# Pizza_IO.net
KiCad netlist of a schematic drawn in Altium Designer
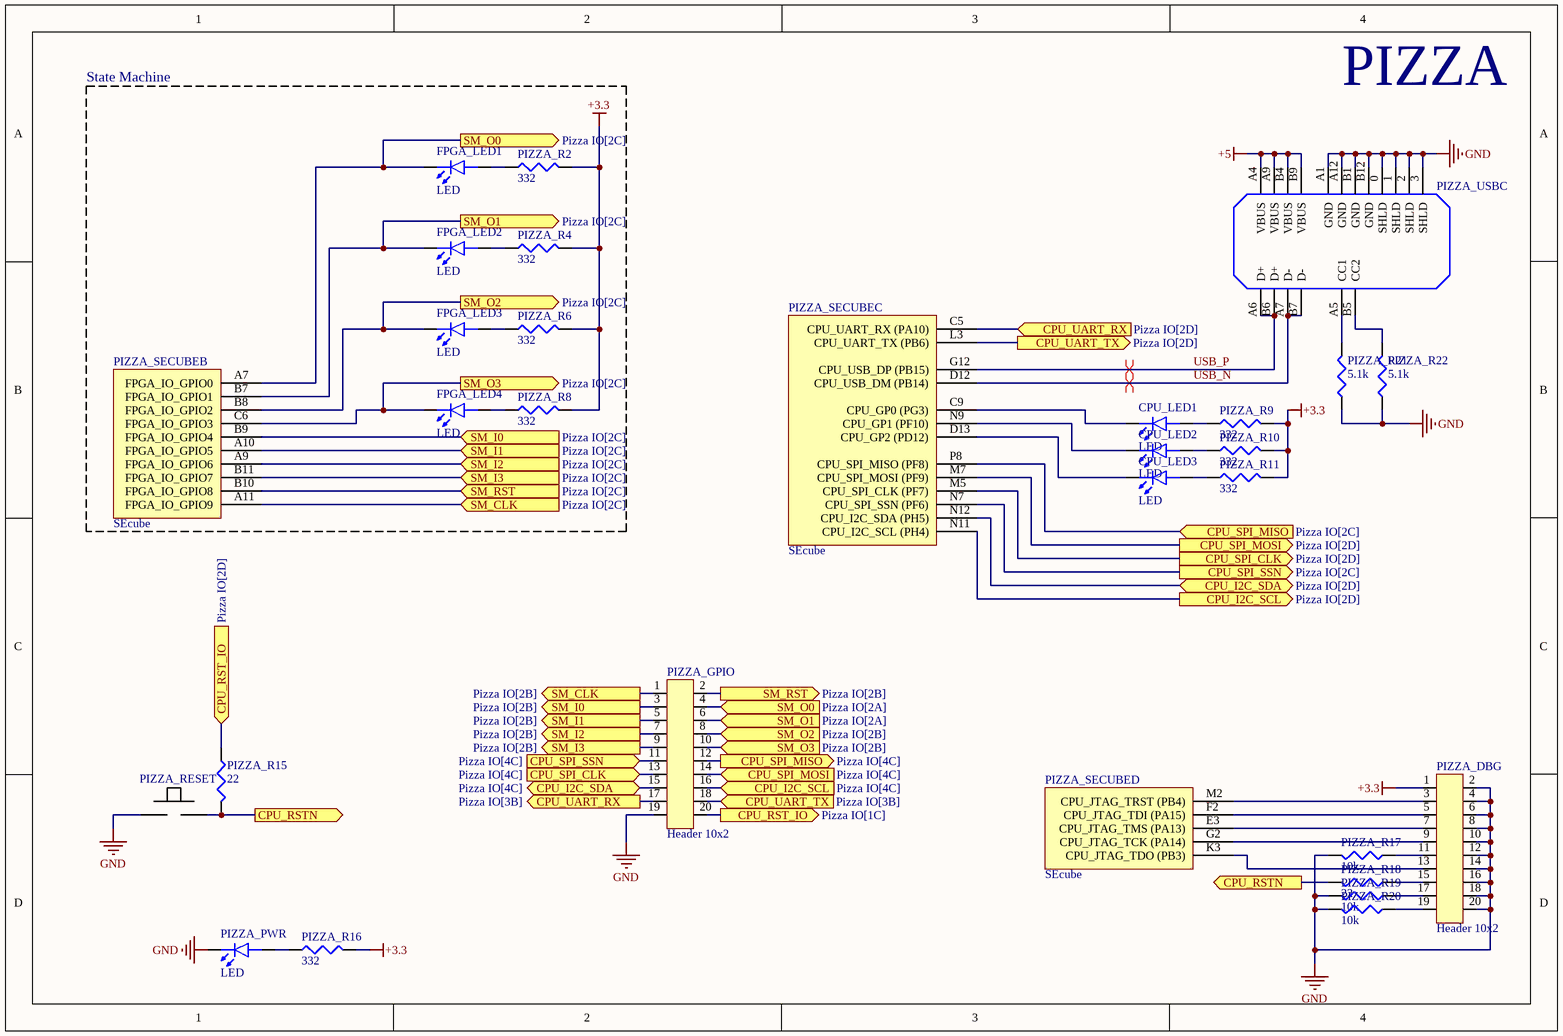
[diagram p0: Pizza IO.SchDoc]

(export (version "E")
  (design (tool "Eeschema 10.0.6"))
  (components
    (comp (ref "CPU_LED1") (value "LED") (footprint "LED0603P") (libsource (lib "ECSC2024") (part "LED")))
    (comp (ref "CPU_LED2") (value "LED") (footprint "LED0603P") (libsource (lib "ECSC2024") (part "LED")))
    (comp (ref "CPU_LED3") (value "LED") (footprint "LED0603P") (libsource (lib "ECSC2024") (part "LED")))
    (comp (ref "FPGA_LED1") (value "LED") (footprint "LED0603P") (libsource (lib "ECSC2024") (part "LED")))
    (comp (ref "FPGA_LED2") (value "LED") (footprint "LED0603P") (libsource (lib "ECSC2024") (part "LED")))
    (comp (ref "FPGA_LED3") (value "LED") (footprint "LED0603P") (libsource (lib "ECSC2024") (part "LED")))
    (comp (ref "FPGA_LED4") (value "LED") (footprint "LED0603P") (libsource (lib "ECSC2024") (part "LED")))
    (comp (ref "PIZZA_DBG")
      (value "Header 10x2")
      (footprint "HEADER10x2")
      (libsource (lib "ECSC2024") (part "Header 10x2"))
    )
    (comp (ref "PIZZA_GPIO")
      (value "Header 10x2")
      (footprint "HEADER10x2")
      (libsource (lib "ECSC2024") (part "Header 10x2"))
    )
    (comp (ref "PIZZA_PWR") (value "LED") (footprint "LED0603P") (libsource (lib "ECSC2024") (part "LED")))
    (comp (ref "PIZZA_R2") (value "332") (footprint "R0402") (libsource (lib "ECSC2024") (part "R")))
    (comp (ref "PIZZA_R4") (value "332") (footprint "R0402") (libsource (lib "ECSC2024") (part "R")))
    (comp (ref "PIZZA_R6") (value "332") (footprint "R0402") (libsource (lib "ECSC2024") (part "R")))
    (comp (ref "PIZZA_R8") (value "332") (footprint "R0402") (libsource (lib "ECSC2024") (part "R")))
    (comp (ref "PIZZA_R9") (value "332") (footprint "R0402") (libsource (lib "ECSC2024") (part "R")))
    (comp (ref "PIZZA_R10") (value "332") (footprint "R0402") (libsource (lib "ECSC2024") (part "R")))
    (comp (ref "PIZZA_R11") (value "332") (footprint "R0402") (libsource (lib "ECSC2024") (part "R")))
    (comp (ref "PIZZA_R15") (value "22") (footprint "R0402") (libsource (lib "ECSC2024") (part "R")))
    (comp (ref "PIZZA_R16") (value "332") (footprint "R0402") (libsource (lib "ECSC2024") (part "R")))
    (comp (ref "PIZZA_R17") (value "10k") (footprint "R0402") (libsource (lib "ECSC2024") (part "R")))
    (comp (ref "PIZZA_R18") (value "22") (footprint "R0402") (libsource (lib "ECSC2024") (part "R")))
    (comp (ref "PIZZA_R19") (value "10k") (footprint "R0402") (libsource (lib "ECSC2024") (part "R")))
    (comp (ref "PIZZA_R20") (value "10k") (footprint "R0402") (libsource (lib "ECSC2024") (part "R")))
    (comp (ref "PIZZA_R21") (value "5.1k") (footprint "R0402") (libsource (lib "ECSC2024") (part "R")))
    (comp (ref "PIZZA_R22") (value "5.1k") (footprint "R0402") (libsource (lib "ECSC2024") (part "R")))
    (comp (ref "PIZZA_RESET")
      (value "BTN")
      (footprint "TS1088AR02016")
      (libsource (lib "ECSC2024") (part "BTN"))
    )
    (comp (ref "PIZZA_SECUBE")
      (value "SEcube")
      (footprint "SEcube")
      (libsource (lib "ECSC2024") (part "SEcube"))
    )
    (comp (ref "PIZZA_USBC")
      (value "USBC")
      (footprint "USB-TYPE-C-018")
      (libsource (lib "ECSC2024") (part "USBC"))
    )
  )
  (nets
    (net (code "1") (name "+3.3") (class "Default")
      (node (ref "PIZZA_DBG") (pin "1") (pintype "passive"))
      (node (ref "PIZZA_R10") (pin "2") (pinfunction "2_2") (pintype "passive"))
      (node (ref "PIZZA_R11") (pin "2") (pinfunction "2_2") (pintype "passive"))
      (node (ref "PIZZA_R16") (pin "2") (pinfunction "2_2") (pintype "passive"))
      (node (ref "PIZZA_R2") (pin "2") (pinfunction "2_2") (pintype "passive"))
      (node (ref "PIZZA_R4") (pin "2") (pinfunction "2_2") (pintype "passive"))
      (node (ref "PIZZA_R6") (pin "2") (pinfunction "2_2") (pintype "passive"))
      (node (ref "PIZZA_R8") (pin "2") (pinfunction "2_2") (pintype "passive"))
      (node (ref "PIZZA_R9") (pin "2") (pinfunction "2_2") (pintype "passive"))
    )
    (net (code "2") (name "+5") (class "Default")
      (node (ref "PIZZA_USBC") (pin "A4") (pinfunction "VBUS_A4") (pintype "passive"))
      (node (ref "PIZZA_USBC") (pin "A9") (pinfunction "VBUS_A9") (pintype "passive"))
      (node (ref "PIZZA_USBC") (pin "B4") (pinfunction "VBUS_B4") (pintype "passive"))
      (node (ref "PIZZA_USBC") (pin "B9") (pinfunction "VBUS_B9") (pintype "passive"))
    )
    (net (code "3") (name "/CPU_I2C_SCL") (class "Default")
      (node (ref "PIZZA_GPIO") (pin "16") (pintype "passive"))
      (node (ref "PIZZA_SECUBE") (pin "N11") (pinfunction "CPU_I2C_SCL_(PH4)_N11") (pintype "passive"))
    )
    (net (code "4") (name "/CPU_I2C_SDA") (class "Default")
      (node (ref "PIZZA_GPIO") (pin "15") (pintype "passive"))
      (node (ref "PIZZA_SECUBE") (pin "N12") (pinfunction "CPU_I2C_SDA_(PH5)_N12") (pintype "passive"))
    )
    (net (code "5") (name "/CPU_RSTN") (class "Default")
      (node (ref "PIZZA_R15") (pin "2") (pinfunction "2_2") (pintype "passive"))
      (node (ref "PIZZA_R18") (pin "2") (pinfunction "2_2") (pintype "passive"))
      (node (ref "PIZZA_RESET") (pin "2") (pinfunction "2_2") (pintype "passive"))
    )
    (net (code "6") (name "/CPU_RST_IO") (class "Default")
      (node (ref "PIZZA_GPIO") (pin "20") (pintype "passive"))
      (node (ref "PIZZA_R15") (pin "1") (pinfunction "1_1") (pintype "passive"))
    )
    (net (code "7") (name "/CPU_SPI_CLK") (class "Default")
      (node (ref "PIZZA_GPIO") (pin "13") (pintype "passive"))
      (node (ref "PIZZA_SECUBE") (pin "M5") (pinfunction "CPU_SPI_CLK_(PF7)_M5") (pintype "passive"))
    )
    (net (code "8") (name "/CPU_SPI_MISO") (class "Default")
      (node (ref "PIZZA_GPIO") (pin "12") (pintype "passive"))
      (node (ref "PIZZA_SECUBE") (pin "P8") (pinfunction "CPU_SPI_MISO_(PF8)_P8") (pintype "passive"))
    )
    (net (code "9") (name "/CPU_SPI_MOSI") (class "Default")
      (node (ref "PIZZA_GPIO") (pin "14") (pintype "passive"))
      (node (ref "PIZZA_SECUBE") (pin "M7") (pinfunction "CPU_SPI_MOSI_(PF9)_M7") (pintype "passive"))
    )
    (net (code "10") (name "/CPU_SPI_SSN") (class "Default")
      (node (ref "PIZZA_GPIO") (pin "11") (pintype "passive"))
      (node (ref "PIZZA_SECUBE") (pin "N7") (pinfunction "CPU_SPI_SSN_(PF6)_N7") (pintype "passive"))
    )
    (net (code "11") (name "/CPU_UART_RX") (class "Default")
      (node (ref "PIZZA_GPIO") (pin "17") (pintype "passive"))
      (node (ref "PIZZA_SECUBE") (pin "C5") (pinfunction "CPU_UART_RX_(PA10)_C5") (pintype "passive"))
    )
    (net (code "12") (name "/CPU_UART_TX") (class "Default")
      (node (ref "PIZZA_GPIO") (pin "18") (pintype "passive"))
      (node (ref "PIZZA_SECUBE") (pin "L3") (pinfunction "CPU_UART_TX_(PB6)_L3") (pintype "passive"))
    )
    (net (code "13") (name "/SM_CLK") (class "Default")
      (node (ref "PIZZA_GPIO") (pin "1") (pintype "passive"))
      (node (ref "PIZZA_SECUBE") (pin "A11") (pinfunction "FPGA_IO_GPIO9_A11") (pintype "passive"))
    )
    (net (code "14") (name "/SM_I0") (class "Default")
      (node (ref "PIZZA_GPIO") (pin "3") (pintype "passive"))
      (node (ref "PIZZA_SECUBE") (pin "B9") (pinfunction "FPGA_IO_GPIO4_B9") (pintype "passive"))
    )
    (net (code "15") (name "/SM_I1") (class "Default")
      (node (ref "PIZZA_GPIO") (pin "5") (pintype "passive"))
      (node (ref "PIZZA_SECUBE") (pin "A10") (pinfunction "FPGA_IO_GPIO5_A10") (pintype "passive"))
    )
    (net (code "16") (name "/SM_I2") (class "Default")
      (node (ref "PIZZA_GPIO") (pin "7") (pintype "passive"))
      (node (ref "PIZZA_SECUBE") (pin "A9") (pinfunction "FPGA_IO_GPIO6_A9") (pintype "passive"))
    )
    (net (code "17") (name "/SM_I3") (class "Default")
      (node (ref "PIZZA_GPIO") (pin "9") (pintype "passive"))
      (node (ref "PIZZA_SECUBE") (pin "B11") (pinfunction "FPGA_IO_GPIO7_B11") (pintype "passive"))
    )
    (net (code "18") (name "/SM_O0") (class "Default")
      (node (ref "FPGA_LED1") (pin "2") (pinfunction "K_2") (pintype "passive"))
      (node (ref "PIZZA_GPIO") (pin "4") (pintype "passive"))
      (node (ref "PIZZA_SECUBE") (pin "A7") (pinfunction "FPGA_IO_GPIO0_A7") (pintype "passive"))
    )
    (net (code "19") (name "/SM_O1") (class "Default")
      (node (ref "FPGA_LED2") (pin "2") (pinfunction "K_2") (pintype "passive"))
      (node (ref "PIZZA_GPIO") (pin "6") (pintype "passive"))
      (node (ref "PIZZA_SECUBE") (pin "B7") (pinfunction "FPGA_IO_GPIO1_B7") (pintype "passive"))
    )
    (net (code "20") (name "/SM_O2") (class "Default")
      (node (ref "FPGA_LED3") (pin "2") (pinfunction "K_2") (pintype "passive"))
      (node (ref "PIZZA_GPIO") (pin "8") (pintype "passive"))
      (node (ref "PIZZA_SECUBE") (pin "B8") (pinfunction "FPGA_IO_GPIO2_B8") (pintype "passive"))
    )
    (net (code "21") (name "/SM_O3") (class "Default")
      (node (ref "FPGA_LED4") (pin "2") (pinfunction "K_2") (pintype "passive"))
      (node (ref "PIZZA_GPIO") (pin "10") (pintype "passive"))
      (node (ref "PIZZA_SECUBE") (pin "C6") (pinfunction "FPGA_IO_GPIO3_C6") (pintype "passive"))
    )
    (net (code "22") (name "/SM_RST") (class "Default")
      (node (ref "PIZZA_GPIO") (pin "2") (pintype "passive"))
      (node (ref "PIZZA_SECUBE") (pin "B10") (pinfunction "FPGA_IO_GPIO8_B10") (pintype "passive"))
    )
    (net (code "23") (name "/USB_N") (class "Default")
      (node (ref "PIZZA_SECUBE") (pin "D12") (pinfunction "CPU_USB_DM_(PB14)_D12") (pintype "passive"))
      (node (ref "PIZZA_USBC") (pin "A7") (pinfunction "D-_A7") (pintype "passive"))
      (node (ref "PIZZA_USBC") (pin "B7") (pinfunction "D-_B7") (pintype "passive"))
    )
    (net (code "24") (name "/USB_P") (class "Default")
      (node (ref "PIZZA_SECUBE") (pin "G12") (pinfunction "CPU_USB_DP_(PB15)_G12") (pintype "passive"))
      (node (ref "PIZZA_USBC") (pin "A6") (pinfunction "D+_A6") (pintype "passive"))
      (node (ref "PIZZA_USBC") (pin "B6") (pinfunction "D+_B6") (pintype "passive"))
    )
    (net (code "25") (name "GND") (class "Default")
      (node (ref "PIZZA_DBG") (pin "10") (pintype "passive"))
      (node (ref "PIZZA_DBG") (pin "12") (pintype "passive"))
      (node (ref "PIZZA_DBG") (pin "14") (pintype "passive"))
      (node (ref "PIZZA_DBG") (pin "16") (pintype "passive"))
      (node (ref "PIZZA_DBG") (pin "18") (pintype "passive"))
      (node (ref "PIZZA_DBG") (pin "2") (pintype "passive"))
      (node (ref "PIZZA_DBG") (pin "20") (pintype "passive"))
      (node (ref "PIZZA_DBG") (pin "4") (pintype "passive"))
      (node (ref "PIZZA_DBG") (pin "6") (pintype "passive"))
      (node (ref "PIZZA_DBG") (pin "8") (pintype "passive"))
      (node (ref "PIZZA_GPIO") (pin "19") (pintype "passive"))
      (node (ref "PIZZA_PWR") (pin "2") (pinfunction "K_2") (pintype "passive"))
      (node (ref "PIZZA_R17") (pin "2") (pinfunction "2_2") (pintype "passive"))
      (node (ref "PIZZA_R19") (pin "2") (pinfunction "2_2") (pintype "passive"))
      (node (ref "PIZZA_R20") (pin "2") (pinfunction "2_2") (pintype "passive"))
      (node (ref "PIZZA_R21") (pin "1") (pinfunction "1_1") (pintype "passive"))
      (node (ref "PIZZA_R22") (pin "1") (pinfunction "1_1") (pintype "passive"))
      (node (ref "PIZZA_RESET") (pin "1") (pinfunction "1_1") (pintype "passive"))
      (node (ref "PIZZA_USBC") (pin "0") (pinfunction "SHLD_0") (pintype "passive"))
      (node (ref "PIZZA_USBC") (pin "1") (pinfunction "SHLD_1") (pintype "passive"))
      (node (ref "PIZZA_USBC") (pin "2") (pinfunction "SHLD_2") (pintype "passive"))
      (node (ref "PIZZA_USBC") (pin "3") (pinfunction "SHLD_3") (pintype "passive"))
      (node (ref "PIZZA_USBC") (pin "A1") (pinfunction "GND_A1") (pintype "passive"))
      (node (ref "PIZZA_USBC") (pin "A12") (pinfunction "GND_A12") (pintype "passive"))
      (node (ref "PIZZA_USBC") (pin "B1") (pinfunction "GND_B1") (pintype "passive"))
      (node (ref "PIZZA_USBC") (pin "B12") (pinfunction "GND_B12") (pintype "passive"))
    )
    (net (code "26") (name "Net-(CPU_LED1-A)") (class "Default")
      (node (ref "CPU_LED1") (pin "1") (pinfunction "A_1") (pintype "passive"))
      (node (ref "PIZZA_R9") (pin "1") (pinfunction "1_1") (pintype "passive"))
    )
    (net (code "27") (name "Net-(CPU_LED1-K)") (class "Default")
      (node (ref "CPU_LED1") (pin "2") (pinfunction "K_2") (pintype "passive"))
      (node (ref "PIZZA_SECUBE") (pin "C9") (pinfunction "CPU_GP0_(PG3)_C9") (pintype "passive"))
    )
    (net (code "28") (name "Net-(CPU_LED2-A)") (class "Default")
      (node (ref "CPU_LED2") (pin "1") (pinfunction "A_1") (pintype "passive"))
      (node (ref "PIZZA_R10") (pin "1") (pinfunction "1_1") (pintype "passive"))
    )
    (net (code "29") (name "Net-(CPU_LED2-K)") (class "Default")
      (node (ref "CPU_LED2") (pin "2") (pinfunction "K_2") (pintype "passive"))
      (node (ref "PIZZA_SECUBE") (pin "N9") (pinfunction "CPU_GP1_(PF10)_N9") (pintype "passive"))
    )
    (net (code "30") (name "Net-(CPU_LED3-A)") (class "Default")
      (node (ref "CPU_LED3") (pin "1") (pinfunction "A_1") (pintype "passive"))
      (node (ref "PIZZA_R11") (pin "1") (pinfunction "1_1") (pintype "passive"))
    )
    (net (code "31") (name "Net-(CPU_LED3-K)") (class "Default")
      (node (ref "CPU_LED3") (pin "2") (pinfunction "K_2") (pintype "passive"))
      (node (ref "PIZZA_SECUBE") (pin "D13") (pinfunction "CPU_GP2_(PD12)_D13") (pintype "passive"))
    )
    (net (code "32") (name "Net-(FPGA_LED1-A)") (class "Default")
      (node (ref "FPGA_LED1") (pin "1") (pinfunction "A_1") (pintype "passive"))
      (node (ref "PIZZA_R2") (pin "1") (pinfunction "1_1") (pintype "passive"))
    )
    (net (code "33") (name "Net-(FPGA_LED2-A)") (class "Default")
      (node (ref "FPGA_LED2") (pin "1") (pinfunction "A_1") (pintype "passive"))
      (node (ref "PIZZA_R4") (pin "1") (pinfunction "1_1") (pintype "passive"))
    )
    (net (code "34") (name "Net-(FPGA_LED3-A)") (class "Default")
      (node (ref "FPGA_LED3") (pin "1") (pinfunction "A_1") (pintype "passive"))
      (node (ref "PIZZA_R6") (pin "1") (pinfunction "1_1") (pintype "passive"))
    )
    (net (code "35") (name "Net-(FPGA_LED4-A)") (class "Default")
      (node (ref "FPGA_LED4") (pin "1") (pinfunction "A_1") (pintype "passive"))
      (node (ref "PIZZA_R8") (pin "1") (pinfunction "1_1") (pintype "passive"))
    )
    (net (code "36") (name "Net-(PIZZA_DBG-Pad11)") (class "Default")
      (node (ref "PIZZA_DBG") (pin "11") (pintype "passive"))
      (node (ref "PIZZA_R17") (pin "1") (pinfunction "1_1") (pintype "passive"))
    )
    (net (code "37") (name "Net-(PIZZA_DBG-Pad15)") (class "Default")
      (node (ref "PIZZA_DBG") (pin "15") (pintype "passive"))
      (node (ref "PIZZA_R18") (pin "1") (pinfunction "1_1") (pintype "passive"))
    )
    (net (code "38") (name "Net-(PIZZA_DBG-Pad17)") (class "Default")
      (node (ref "PIZZA_DBG") (pin "17") (pintype "passive"))
      (node (ref "PIZZA_R19") (pin "1") (pinfunction "1_1") (pintype "passive"))
    )
    (net (code "39") (name "Net-(PIZZA_DBG-Pad19)") (class "Default")
      (node (ref "PIZZA_DBG") (pin "19") (pintype "passive"))
      (node (ref "PIZZA_R20") (pin "1") (pinfunction "1_1") (pintype "passive"))
    )
    (net (code "40") (name "Net-(PIZZA_PWR-A)") (class "Default")
      (node (ref "PIZZA_PWR") (pin "1") (pinfunction "A_1") (pintype "passive"))
      (node (ref "PIZZA_R16") (pin "1") (pinfunction "1_1") (pintype "passive"))
    )
    (net (code "41") (name "Net-(PIZZA_SECUBED-CPU_JTAG_TCK_(PA14))") (class "Default")
      (node (ref "PIZZA_DBG") (pin "9") (pintype "passive"))
      (node (ref "PIZZA_SECUBE") (pin "G2") (pinfunction "CPU_JTAG_TCK_(PA14)_G2") (pintype "passive"))
    )
    (net (code "42") (name "Net-(PIZZA_SECUBED-CPU_JTAG_TDI_(PA15))") (class "Default")
      (node (ref "PIZZA_DBG") (pin "5") (pintype "passive"))
      (node (ref "PIZZA_SECUBE") (pin "F2") (pinfunction "CPU_JTAG_TDI_(PA15)_F2") (pintype "passive"))
    )
    (net (code "43") (name "Net-(PIZZA_SECUBED-CPU_JTAG_TDO_(PB3))") (class "Default")
      (node (ref "PIZZA_DBG") (pin "13") (pintype "passive"))
      (node (ref "PIZZA_SECUBE") (pin "K3") (pinfunction "CPU_JTAG_TDO_(PB3)_K3") (pintype "passive"))
    )
    (net (code "44") (name "Net-(PIZZA_SECUBED-CPU_JTAG_TMS_(PA13))") (class "Default")
      (node (ref "PIZZA_DBG") (pin "7") (pintype "passive"))
      (node (ref "PIZZA_SECUBE") (pin "E3") (pinfunction "CPU_JTAG_TMS_(PA13)_E3") (pintype "passive"))
    )
    (net (code "45") (name "Net-(PIZZA_SECUBED-CPU_JTAG_TRST_(PB4))") (class "Default")
      (node (ref "PIZZA_DBG") (pin "3") (pintype "passive"))
      (node (ref "PIZZA_SECUBE") (pin "M2") (pinfunction "CPU_JTAG_TRST_(PB4)_M2") (pintype "passive"))
    )
    (net (code "46") (name "Net-(PIZZA_USBC-CC1)") (class "Default")
      (node (ref "PIZZA_R21") (pin "2") (pinfunction "2_2") (pintype "passive"))
      (node (ref "PIZZA_USBC") (pin "A5") (pinfunction "CC1_A5") (pintype "passive"))
    )
    (net (code "47") (name "Net-(PIZZA_USBC-CC2)") (class "Default")
      (node (ref "PIZZA_R22") (pin "2") (pinfunction "2_2") (pintype "passive"))
      (node (ref "PIZZA_USBC") (pin "B5") (pinfunction "CC2_B5") (pintype "passive"))
    )
  )
)
